# detector328p-au.net
KiCad netlist of a schematic drawn in EAGLE
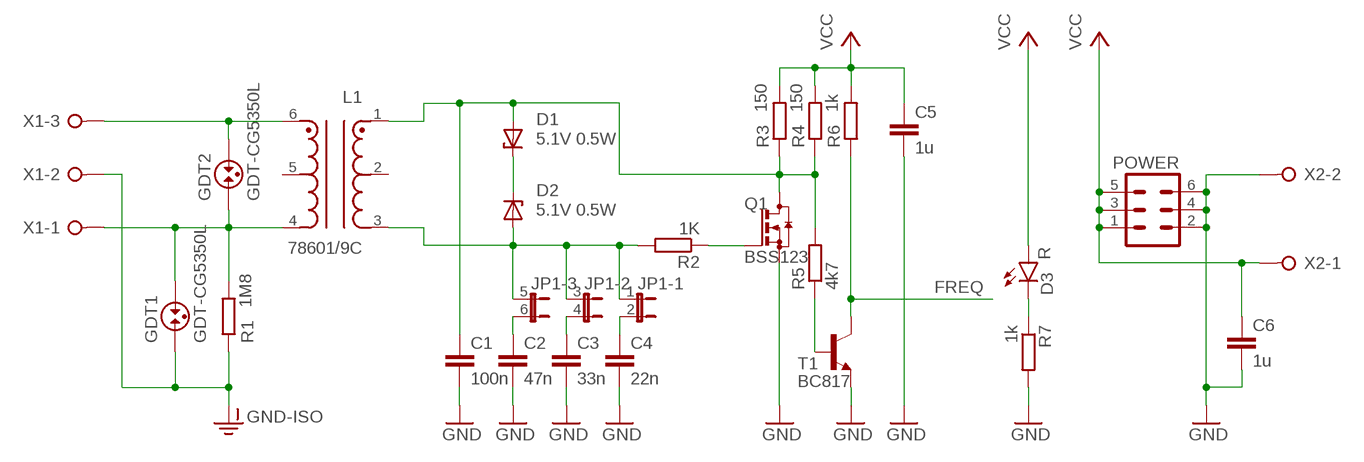
[diagram p0: schematic, sheet 1]
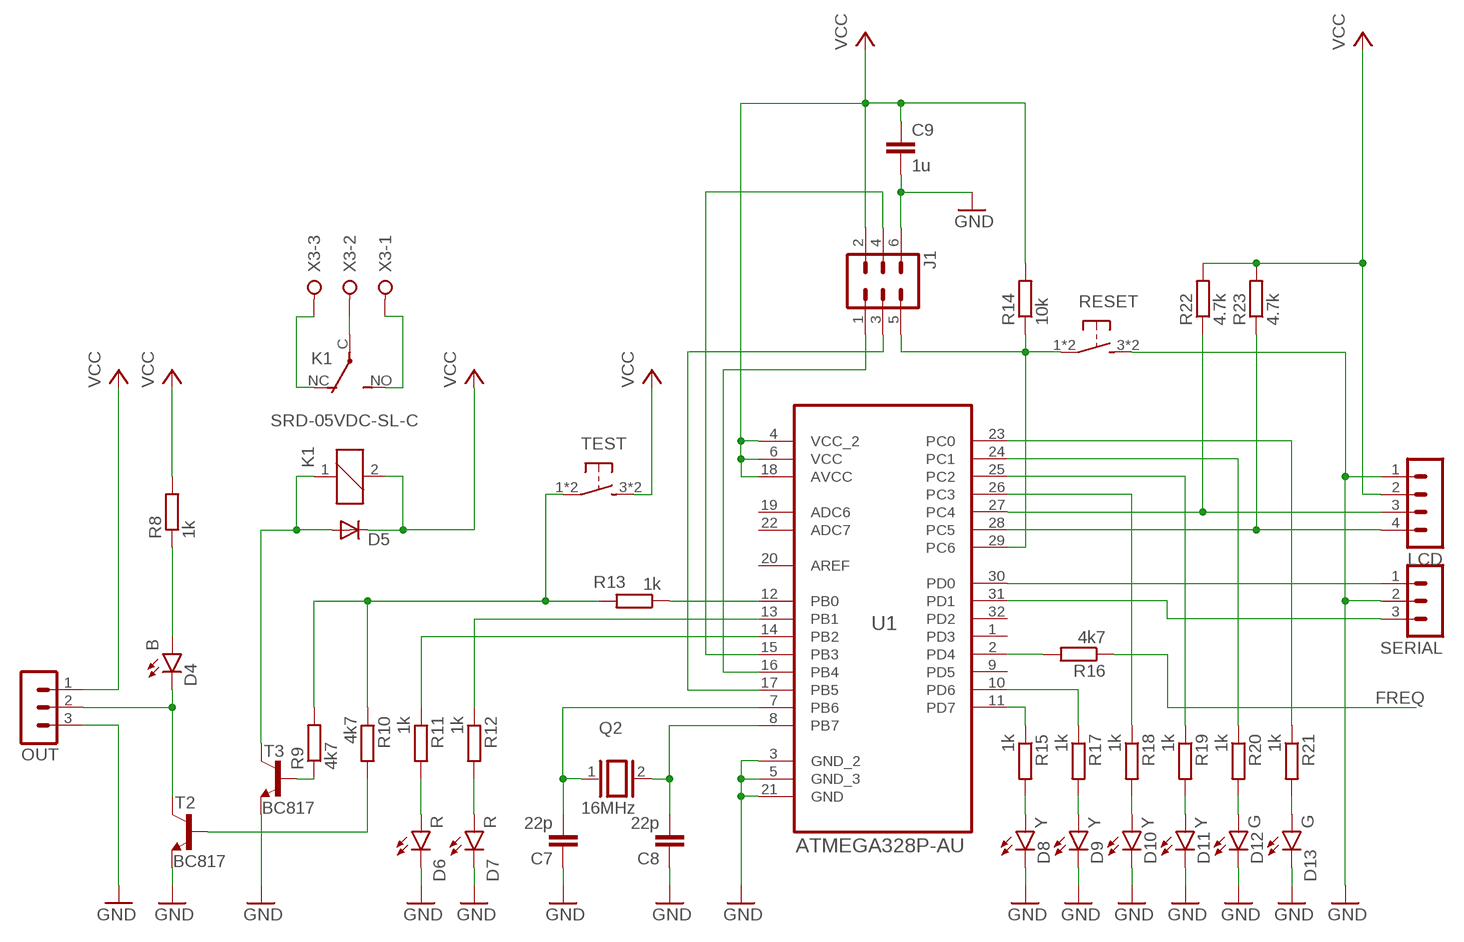
[diagram p1: schematic, sheet 2]

(export (version "E")
  (design (tool "Eeschema 10.0.6"))
  (components
    (comp (ref "C1")
      (value "100n")
      (footprint "eagle-import:C0603")
      (libsource (lib "eagle-import") (part "resistor_C-EUC0603"))
    )
    (comp (ref "C2")
      (value "47n")
      (footprint "eagle-import:C0603")
      (libsource (lib "eagle-import") (part "resistor_C-EUC0603"))
    )
    (comp (ref "C3")
      (value "33n")
      (footprint "eagle-import:C0603")
      (libsource (lib "eagle-import") (part "resistor_C-EUC0603"))
    )
    (comp (ref "C4")
      (value "22n")
      (footprint "eagle-import:C0603")
      (libsource (lib "eagle-import") (part "resistor_C-EUC0603"))
    )
    (comp (ref "C5")
      (value "1u")
      (footprint "eagle-import:C0603")
      (libsource (lib "eagle-import") (part "C-EUC0603"))
    )
    (comp (ref "C6")
      (value "1u")
      (footprint "eagle-import:C0603")
      (libsource (lib "eagle-import") (part "C-EUC0603"))
    )
    (comp (ref "D1")
      (value "5.1V 0.5W")
      (footprint "eagle-import:SOD80C")
      (libsource (lib "eagle-import") (part "ZENER-DIODESOD80C"))
    )
    (comp (ref "D2")
      (value "5.1V 0.5W")
      (footprint "eagle-import:SOD80C")
      (libsource (lib "eagle-import") (part "ZENER-DIODESOD80C"))
    )
    (comp (ref "D3")
      (value "R")
      (footprint "eagle-import:LED-0603")
      (libsource (lib "eagle-import") (part "LED0603"))
    )
    (comp (ref "GDT1")
      (value "GDT-CG5350L")
      (footprint "eagle-import:CG5350L")
      (libsource (lib "eagle-import") (part "GDT-CG5350L"))
    )
    (comp (ref "GDT2")
      (value "GDT-CG5350L")
      (footprint "eagle-import:CG5350L")
      (libsource (lib "eagle-import") (part "GDT-CG5350L"))
    )
    (comp (ref "JP1")
      (value "JP3QE")
      (footprint "eagle-import:JP3Q")
      (libsource (lib "eagle-import") (part "JP3QE"))
    )
    (comp (ref "L1")
      (value "78601/9C")
      (footprint "eagle-import:78601_9C")
      (libsource (lib "eagle-import") (part "78601/9C"))
    )
    (comp (ref "POWER")
      (value "MA03-2")
      (footprint "eagle-import:MA03-2")
      (libsource (lib "eagle-import") (part "MA03-2"))
    )
    (comp (ref "Q1")
      (value "BSS123")
      (footprint "eagle-import:SOT23")
      (libsource (lib "eagle-import") (part "BSS123"))
    )
    (comp (ref "R1")
      (value "1M8")
      (footprint "eagle-import:R0603")
      (libsource (lib "eagle-import") (part "resistor_R-EU_R0603"))
    )
    (comp (ref "R2")
      (value "1K")
      (footprint "eagle-import:R0603")
      (libsource (lib "eagle-import") (part "resistor_R-EU_R0603"))
    )
    (comp (ref "R3")
      (value "150")
      (footprint "eagle-import:R0603")
      (libsource (lib "eagle-import") (part "resistor_R-EU_R0603"))
    )
    (comp (ref "R4")
      (value "150")
      (footprint "eagle-import:R0603")
      (libsource (lib "eagle-import") (part "resistor_R-EU_R0603"))
    )
    (comp (ref "R5")
      (value "4k7")
      (footprint "eagle-import:R0603")
      (libsource (lib "eagle-import") (part "resistor_R-EU_R0603"))
    )
    (comp (ref "R6")
      (value "1k")
      (footprint "eagle-import:R0603")
      (libsource (lib "eagle-import") (part "resistor_R-EU_R0603"))
    )
    (comp (ref "R7")
      (value "1k")
      (footprint "eagle-import:R0603")
      (libsource (lib "eagle-import") (part "resistor_R-EU_R0603"))
    )
    (comp (ref "T1")
      (value "BC817")
      (footprint "eagle-import:SOT23-BEC")
      (libsource (lib "eagle-import") (part "BC817SMD-40"))
    )
    (comp (ref "X1")
      (value "W237-3E")
      (footprint "eagle-import:W237-3E")
      (libsource (lib "eagle-import") (part "W237-3E"))
    )
    (comp (ref "X2")
      (value "W237-02P")
      (footprint "eagle-import:W237-132")
      (libsource (lib "eagle-import") (part "W237-02P"))
    )
    (comp (ref "C7")
      (value "22p")
      (footprint "eagle-import:C0603")
      (libsource (lib "eagle-import") (part "resistor_C-EUC0603"))
    )
    (comp (ref "C8")
      (value "22p")
      (footprint "eagle-import:C0603")
      (libsource (lib "eagle-import") (part "resistor_C-EUC0603"))
    )
    (comp (ref "C9")
      (value "1u")
      (footprint "eagle-import:C0603")
      (libsource (lib "eagle-import") (part "C-EUC0603"))
    )
    (comp (ref "D4")
      (value "B")
      (footprint "eagle-import:LED-0603")
      (libsource (lib "eagle-import") (part "LED0603"))
    )
    (comp (ref "D5")
      (value "DIODE-SOD80C")
      (footprint "eagle-import:SOD80C")
      (libsource (lib "eagle-import") (part "DIODE-SOD80C"))
    )
    (comp (ref "D6")
      (value "R")
      (footprint "eagle-import:LED-0603")
      (libsource (lib "eagle-import") (part "LED0603"))
    )
    (comp (ref "D7")
      (value "R")
      (footprint "eagle-import:LED-0603")
      (libsource (lib "eagle-import") (part "LED0603"))
    )
    (comp (ref "D8")
      (value "Y")
      (footprint "eagle-import:LED-0603")
      (libsource (lib "eagle-import") (part "LED0603"))
    )
    (comp (ref "D9")
      (value "Y")
      (footprint "eagle-import:LED-0603")
      (libsource (lib "eagle-import") (part "LED0603"))
    )
    (comp (ref "D10")
      (value "Y")
      (footprint "eagle-import:LED-0603")
      (libsource (lib "eagle-import") (part "LED0603"))
    )
    (comp (ref "D11")
      (value "Y")
      (footprint "eagle-import:LED-0603")
      (libsource (lib "eagle-import") (part "LED0603"))
    )
    (comp (ref "D12")
      (value "G")
      (footprint "eagle-import:LED-0603")
      (libsource (lib "eagle-import") (part "LED0603"))
    )
    (comp (ref "D13")
      (value "G")
      (footprint "eagle-import:LED-0603")
      (libsource (lib "eagle-import") (part "LED0603"))
    )
    (comp (ref "J1")
      (value "MA03-2")
      (footprint "eagle-import:MA03-2")
      (libsource (lib "eagle-import") (part "MA03-2"))
    )
    (comp (ref "K1")
      (value "SRD-05VDC-SL-C")
      (footprint "eagle-import:JS-M")
      (libsource (lib "eagle-import") (part "SRD--SL-C05VDC"))
    )
    (comp (ref "LCD")
      (value "MA04-1")
      (footprint "eagle-import:MA04-1")
      (libsource (lib "eagle-import") (part "MA04-1"))
    )
    (comp (ref "OUT")
      (value "MA03-1")
      (footprint "eagle-import:MA03-1")
      (libsource (lib "eagle-import") (part "MA03-1"))
    )
    (comp (ref "Q2")
      (value "16MHz")
      (footprint "eagle-import:QS")
      (libsource (lib "eagle-import") (part "XTAL/S"))
    )
    (comp (ref "R8")
      (value "1k")
      (footprint "eagle-import:R0603")
      (libsource (lib "eagle-import") (part "resistor_R-EU_R0603"))
    )
    (comp (ref "R9")
      (value "4k7")
      (footprint "eagle-import:R0603")
      (libsource (lib "eagle-import") (part "resistor_R-EU_R0603"))
    )
    (comp (ref "R10")
      (value "4k7")
      (footprint "eagle-import:R0603")
      (libsource (lib "eagle-import") (part "resistor_R-EU_R0603"))
    )
    (comp (ref "R11")
      (value "1k")
      (footprint "eagle-import:R0603")
      (libsource (lib "eagle-import") (part "resistor_R-EU_R0603"))
    )
    (comp (ref "R12")
      (value "1k")
      (footprint "eagle-import:R0603")
      (libsource (lib "eagle-import") (part "resistor_R-EU_R0603"))
    )
    (comp (ref "R13")
      (value "1k")
      (footprint "eagle-import:R0603")
      (libsource (lib "eagle-import") (part "resistor_R-EU_R0603"))
    )
    (comp (ref "R14")
      (value "10k")
      (footprint "eagle-import:R0603")
      (libsource (lib "eagle-import") (part "resistor_R-EU_R0603"))
    )
    (comp (ref "R15")
      (value "1k")
      (footprint "eagle-import:R0603")
      (libsource (lib "eagle-import") (part "resistor_R-EU_R0603"))
    )
    (comp (ref "R16")
      (value "4k7")
      (footprint "eagle-import:R0603")
      (libsource (lib "eagle-import") (part "resistor_R-EU_R0603"))
    )
    (comp (ref "R17")
      (value "1k")
      (footprint "eagle-import:R0603")
      (libsource (lib "eagle-import") (part "resistor_R-EU_R0603"))
    )
    (comp (ref "R18")
      (value "1k")
      (footprint "eagle-import:R0603")
      (libsource (lib "eagle-import") (part "resistor_R-EU_R0603"))
    )
    (comp (ref "R19")
      (value "1k")
      (footprint "eagle-import:R0603")
      (libsource (lib "eagle-import") (part "resistor_R-EU_R0603"))
    )
    (comp (ref "R20")
      (value "1k")
      (footprint "eagle-import:R0603")
      (libsource (lib "eagle-import") (part "resistor_R-EU_R0603"))
    )
    (comp (ref "R21")
      (value "1k")
      (footprint "eagle-import:R0603")
      (libsource (lib "eagle-import") (part "resistor_R-EU_R0603"))
    )
    (comp (ref "R22")
      (value "4.7k")
      (footprint "eagle-import:R0603")
      (libsource (lib "eagle-import") (part "R-EU_R0603"))
    )
    (comp (ref "R23")
      (value "4.7k")
      (footprint "eagle-import:R0603")
      (libsource (lib "eagle-import") (part "R-EU_R0603"))
    )
    (comp (ref "RESET")
      (value "10-XX")
      (footprint "eagle-import:B3F-10XX")
      (fields (field (name "MPN") "B3F-1000"))
      (libsource (lib "eagle-import") (part "10-XX"))
    )
    (comp (ref "SERIAL")
      (value "MA03-1")
      (footprint "eagle-import:MA03-1")
      (libsource (lib "eagle-import") (part "MA03-1"))
    )
    (comp (ref "T2")
      (value "BC817")
      (footprint "eagle-import:SOT23-BEC")
      (libsource (lib "eagle-import") (part "BC817SMD-40"))
    )
    (comp (ref "T3")
      (value "BC817")
      (footprint "eagle-import:SOT23-BEC")
      (libsource (lib "eagle-import") (part "BC817SMD-40"))
    )
    (comp (ref "TEST")
      (value "10-XX")
      (footprint "eagle-import:B3F-10XX")
      (fields (field (name "MPN") "B3F-1000"))
      (libsource (lib "eagle-import") (part "10-XX"))
    )
    (comp (ref "U1")
      (value "ATMEGA328P-AU")
      (footprint "eagle-import:QFP80P900X900X120-32N")
      (libsource (lib "eagle-import") (part "ATMEGA328P-AU"))
    )
    (comp (ref "X3")
      (value "W237-3E")
      (footprint "eagle-import:W237-3E")
      (libsource (lib "eagle-import") (part "W237-3E"))
    )
  )
  (nets
    (net (code "1") (name "FREQ") (class "Default")
      (node (ref "R16") (pin "1") (pinfunction "1_1") (pintype "passive"))
      (node (ref "R6") (pin "1") (pinfunction "1_1") (pintype "passive"))
      (node (ref "T1") (pin "C") (pinfunction "C_C") (pintype "passive"))
    )
    (net (code "2") (name "GND") (class "Default")
      (node (ref "C1") (pin "2") (pinfunction "2_2") (pintype "passive"))
      (node (ref "C2") (pin "2") (pinfunction "2_2") (pintype "passive"))
      (node (ref "C3") (pin "2") (pinfunction "2_2") (pintype "passive"))
      (node (ref "C4") (pin "2") (pinfunction "2_2") (pintype "passive"))
      (node (ref "C5") (pin "2") (pinfunction "2_2") (pintype "passive"))
      (node (ref "C6") (pin "2") (pinfunction "2_2") (pintype "passive"))
      (node (ref "C7") (pin "1") (pinfunction "1_1") (pintype "passive"))
      (node (ref "C8") (pin "1") (pinfunction "1_1") (pintype "passive"))
      (node (ref "C9") (pin "2") (pinfunction "2_2") (pintype "passive"))
      (node (ref "D10") (pin "C") (pinfunction "C_C") (pintype "passive"))
      (node (ref "D11") (pin "C") (pinfunction "C_C") (pintype "passive"))
      (node (ref "D12") (pin "C") (pinfunction "C_C") (pintype "passive"))
      (node (ref "D13") (pin "C") (pinfunction "C_C") (pintype "passive"))
      (node (ref "D6") (pin "C") (pinfunction "C_C") (pintype "passive"))
      (node (ref "D7") (pin "C") (pinfunction "C_C") (pintype "passive"))
      (node (ref "D8") (pin "C") (pinfunction "C_C") (pintype "passive"))
      (node (ref "D9") (pin "C") (pinfunction "C_C") (pintype "passive"))
      (node (ref "J1") (pin "6") (pinfunction "6_6") (pintype "passive"))
      (node (ref "LCD") (pin "1") (pinfunction "1_1") (pintype "passive"))
      (node (ref "OUT") (pin "3") (pinfunction "3_3") (pintype "passive"))
      (node (ref "POWER") (pin "2") (pinfunction "2_2") (pintype "passive"))
      (node (ref "POWER") (pin "4") (pinfunction "4_4") (pintype "passive"))
      (node (ref "POWER") (pin "6") (pinfunction "6_6") (pintype "passive"))
      (node (ref "Q1") (pin "2") (pinfunction "S_2") (pintype "passive"))
      (node (ref "R7") (pin "2") (pinfunction "2_2") (pintype "passive"))
      (node (ref "RESET") (pin "3") (pinfunction "S_3") (pintype "passive"))
      (node (ref "RESET") (pin "4") (pinfunction "S_4") (pintype "passive"))
      (node (ref "SERIAL") (pin "2") (pinfunction "2_2") (pintype "passive"))
      (node (ref "T1") (pin "E") (pinfunction "E_E") (pintype "passive"))
      (node (ref "T2") (pin "E") (pinfunction "E_E") (pintype "passive"))
      (node (ref "T3") (pin "E") (pinfunction "E_E") (pintype "passive"))
      (node (ref "U1") (pin "21") (pinfunction "GND_21") (pintype "passive"))
      (node (ref "U1") (pin "3") (pinfunction "GND_2_3") (pintype "passive"))
      (node (ref "U1") (pin "5") (pinfunction "GND_3_5") (pintype "passive"))
      (node (ref "X2") (pin "2") (pinfunction "KL_2") (pintype "passive"))
    )
    (net (code "3") (name "GND-ISO") (class "Default")
      (node (ref "GDT1") (pin "1") (pinfunction "1_1") (pintype "passive"))
      (node (ref "R1") (pin "1") (pinfunction "1_1") (pintype "passive"))
      (node (ref "X1") (pin "2") (pinfunction "KL_2") (pintype "passive"))
    )
    (net (code "4") (name "Net-(C4-Pad1)") (class "Default")
      (node (ref "C4") (pin "1") (pinfunction "1_1") (pintype "passive"))
      (node (ref "JP1") (pin "2") (pinfunction "2_2") (pintype "passive"))
    )
    (net (code "5") (name "Net-(D1-PadC)") (class "Default")
      (node (ref "D1") (pin "C") (pinfunction "C_C") (pintype "passive"))
      (node (ref "D2") (pin "C") (pinfunction "C_C") (pintype "passive"))
    )
    (net (code "6") (name "Net-(D3-PadC)") (class "Default")
      (node (ref "D3") (pin "C") (pinfunction "C_C") (pintype "passive"))
      (node (ref "R7") (pin "1") (pinfunction "1_1") (pintype "passive"))
    )
    (net (code "7") (name "Net-(D4-PadA)") (class "Default")
      (node (ref "D4") (pin "A") (pinfunction "A_A") (pintype "passive"))
      (node (ref "R8") (pin "1") (pinfunction "1_1") (pintype "passive"))
    )
    (net (code "8") (name "Net-(D4-PadC)") (class "Default")
      (node (ref "D4") (pin "C") (pinfunction "C_C") (pintype "passive"))
      (node (ref "OUT") (pin "2") (pinfunction "2_2") (pintype "passive"))
      (node (ref "T2") (pin "C") (pinfunction "C_C") (pintype "passive"))
    )
    (net (code "9") (name "Net-(D5-PadA)") (class "Default")
      (node (ref "D5") (pin "A") (pinfunction "A_A") (pintype "passive"))
      (node (ref "K1") (pin "1") (pinfunction "1_1") (pintype "passive"))
      (node (ref "T3") (pin "C") (pinfunction "C_C") (pintype "passive"))
    )
    (net (code "10") (name "Net-(D6-PadA)") (class "Default")
      (node (ref "D6") (pin "A") (pinfunction "A_A") (pintype "passive"))
      (node (ref "R11") (pin "2") (pinfunction "2_2") (pintype "passive"))
    )
    (net (code "11") (name "Net-(D7-PadA)") (class "Default")
      (node (ref "D7") (pin "A") (pinfunction "A_A") (pintype "passive"))
      (node (ref "R12") (pin "2") (pinfunction "2_2") (pintype "passive"))
    )
    (net (code "12") (name "Net-(D8-PadA)") (class "Default")
      (node (ref "D8") (pin "A") (pinfunction "A_A") (pintype "passive"))
      (node (ref "R15") (pin "2") (pinfunction "2_2") (pintype "passive"))
    )
    (net (code "13") (name "Net-(D9-PadA)") (class "Default")
      (node (ref "D9") (pin "A") (pinfunction "A_A") (pintype "passive"))
      (node (ref "R17") (pin "2") (pinfunction "2_2") (pintype "passive"))
    )
    (net (code "14") (name "Net-(D10-PadA)") (class "Default")
      (node (ref "D10") (pin "A") (pinfunction "A_A") (pintype "passive"))
      (node (ref "R18") (pin "2") (pinfunction "2_2") (pintype "passive"))
    )
    (net (code "15") (name "Net-(D11-PadA)") (class "Default")
      (node (ref "D11") (pin "A") (pinfunction "A_A") (pintype "passive"))
      (node (ref "R19") (pin "2") (pinfunction "2_2") (pintype "passive"))
    )
    (net (code "16") (name "Net-(D12-PadA)") (class "Default")
      (node (ref "D12") (pin "A") (pinfunction "A_A") (pintype "passive"))
      (node (ref "R20") (pin "2") (pinfunction "2_2") (pintype "passive"))
    )
    (net (code "17") (name "Net-(D13-PadA)") (class "Default")
      (node (ref "D13") (pin "A") (pinfunction "A_A") (pintype "passive"))
      (node (ref "R21") (pin "2") (pinfunction "2_2") (pintype "passive"))
    )
    (net (code "18") (name "Net-(JP1B-1)") (class "Default")
      (node (ref "D2") (pin "A") (pinfunction "A_A") (pintype "passive"))
      (node (ref "JP1") (pin "1") (pinfunction "1_1") (pintype "passive"))
      (node (ref "JP1") (pin "3") (pinfunction "1_3") (pintype "passive"))
      (node (ref "JP1") (pin "5") (pinfunction "1_5") (pintype "passive"))
      (node (ref "L1") (pin "3") (pinfunction "3_3") (pintype "passive"))
      (node (ref "R2") (pin "2") (pinfunction "2_2") (pintype "passive"))
    )
    (net (code "19") (name "Net-(JP1B-2)") (class "Default")
      (node (ref "C3") (pin "1") (pinfunction "1_1") (pintype "passive"))
      (node (ref "JP1") (pin "4") (pinfunction "2_4") (pintype "passive"))
    )
    (net (code "20") (name "Net-(JP1C-2)") (class "Default")
      (node (ref "C2") (pin "1") (pinfunction "1_1") (pintype "passive"))
      (node (ref "JP1") (pin "6") (pinfunction "2_6") (pintype "passive"))
    )
    (net (code "21") (name "Net-(K1B-O)") (class "Default")
      (node (ref "K1") (pin "NC") (pinfunction "O_NC") (pintype "passive"))
      (node (ref "X3") (pin "3") (pinfunction "KL_3") (pintype "passive"))
    )
    (net (code "22") (name "Net-(K1B-P)") (class "Default")
      (node (ref "K1") (pin "C") (pinfunction "P_C") (pintype "passive"))
      (node (ref "X3") (pin "2") (pinfunction "KL_2") (pintype "passive"))
    )
    (net (code "23") (name "Net-(K1B-S)") (class "Default")
      (node (ref "K1") (pin "NO") (pinfunction "S_NO") (pintype "passive"))
      (node (ref "X3") (pin "1") (pinfunction "KL_1") (pintype "passive"))
    )
    (net (code "24") (name "Net-(Q1-D)") (class "Default")
      (node (ref "C1") (pin "1") (pinfunction "1_1") (pintype "passive"))
      (node (ref "D1") (pin "A") (pinfunction "A_A") (pintype "passive"))
      (node (ref "L1") (pin "1") (pinfunction "1_1") (pintype "passive"))
      (node (ref "Q1") (pin "3") (pinfunction "D_3") (pintype "passive"))
      (node (ref "R3") (pin "1") (pinfunction "1_1") (pintype "passive"))
      (node (ref "R4") (pin "1") (pinfunction "1_1") (pintype "passive"))
      (node (ref "R5") (pin "2") (pinfunction "2_2") (pintype "passive"))
    )
    (net (code "25") (name "Net-(Q1-G)") (class "Default")
      (node (ref "Q1") (pin "1") (pinfunction "G_1") (pintype "passive"))
      (node (ref "R2") (pin "1") (pinfunction "1_1") (pintype "passive"))
    )
    (net (code "26") (name "Net-(R5-Pad1)") (class "Default")
      (node (ref "R5") (pin "1") (pinfunction "1_1") (pintype "passive"))
      (node (ref "T1") (pin "B") (pinfunction "B_B") (pintype "passive"))
    )
    (net (code "27") (name "Net-(R9-Pad1)") (class "Default")
      (node (ref "R9") (pin "1") (pinfunction "1_1") (pintype "passive"))
      (node (ref "T3") (pin "B") (pinfunction "B_B") (pintype "passive"))
    )
    (net (code "28") (name "Net-(R10-Pad1)") (class "Default")
      (node (ref "R10") (pin "1") (pinfunction "1_1") (pintype "passive"))
      (node (ref "R13") (pin "2") (pinfunction "2_2") (pintype "passive"))
      (node (ref "R9") (pin "2") (pinfunction "2_2") (pintype "passive"))
      (node (ref "TEST") (pin "1") (pinfunction "P_1") (pintype "passive"))
      (node (ref "TEST") (pin "2") (pinfunction "P_2") (pintype "passive"))
    )
    (net (code "29") (name "Net-(R10-Pad2)") (class "Default")
      (node (ref "R10") (pin "2") (pinfunction "2_2") (pintype "passive"))
      (node (ref "T2") (pin "B") (pinfunction "B_B") (pintype "passive"))
    )
    (net (code "30") (name "Net-(U1-PB0)") (class "Default")
      (node (ref "R13") (pin "1") (pinfunction "1_1") (pintype "passive"))
      (node (ref "U1") (pin "12") (pinfunction "PB0_12") (pintype "bidirectional"))
    )
    (net (code "31") (name "Net-(U1-PB1)") (class "Default")
      (node (ref "R12") (pin "1") (pinfunction "1_1") (pintype "passive"))
      (node (ref "U1") (pin "13") (pinfunction "PB1_13") (pintype "bidirectional"))
    )
    (net (code "32") (name "Net-(U1-PB2)") (class "Default")
      (node (ref "R11") (pin "1") (pinfunction "1_1") (pintype "passive"))
      (node (ref "U1") (pin "14") (pinfunction "PB2_14") (pintype "bidirectional"))
    )
    (net (code "33") (name "Net-(U1-PB3)") (class "Default")
      (node (ref "J1") (pin "4") (pinfunction "4_4") (pintype "passive"))
      (node (ref "U1") (pin "15") (pinfunction "PB3_15") (pintype "bidirectional"))
    )
    (net (code "34") (name "Net-(U1-PB4)") (class "Default")
      (node (ref "J1") (pin "1") (pinfunction "1_1") (pintype "passive"))
      (node (ref "U1") (pin "16") (pinfunction "PB4_16") (pintype "bidirectional"))
    )
    (net (code "35") (name "Net-(U1-PB5)") (class "Default")
      (node (ref "J1") (pin "3") (pinfunction "3_3") (pintype "passive"))
      (node (ref "U1") (pin "17") (pinfunction "PB5_17") (pintype "bidirectional"))
    )
    (net (code "36") (name "Net-(U1-PB6)") (class "Default")
      (node (ref "C7") (pin "2") (pinfunction "2_2") (pintype "passive"))
      (node (ref "Q2") (pin "1") (pinfunction "1_1") (pintype "passive"))
      (node (ref "U1") (pin "7") (pinfunction "PB6_7") (pintype "bidirectional"))
    )
    (net (code "37") (name "Net-(U1-PB7)") (class "Default")
      (node (ref "C8") (pin "2") (pinfunction "2_2") (pintype "passive"))
      (node (ref "Q2") (pin "2") (pinfunction "2_2") (pintype "passive"))
      (node (ref "U1") (pin "8") (pinfunction "PB7_8") (pintype "bidirectional"))
    )
    (net (code "38") (name "Net-(U1-PC0)") (class "Default")
      (node (ref "R21") (pin "1") (pinfunction "1_1") (pintype "passive"))
      (node (ref "U1") (pin "23") (pinfunction "PC0_23") (pintype "bidirectional"))
    )
    (net (code "39") (name "Net-(U1-PC1)") (class "Default")
      (node (ref "R20") (pin "1") (pinfunction "1_1") (pintype "passive"))
      (node (ref "U1") (pin "24") (pinfunction "PC1_24") (pintype "bidirectional"))
    )
    (net (code "40") (name "Net-(U1-PC2)") (class "Default")
      (node (ref "R19") (pin "1") (pinfunction "1_1") (pintype "passive"))
      (node (ref "U1") (pin "25") (pinfunction "PC2_25") (pintype "bidirectional"))
    )
    (net (code "41") (name "Net-(U1-PC3)") (class "Default")
      (node (ref "R18") (pin "1") (pinfunction "1_1") (pintype "passive"))
      (node (ref "U1") (pin "26") (pinfunction "PC3_26") (pintype "bidirectional"))
    )
    (net (code "42") (name "Net-(U1-PC4)") (class "Default")
      (node (ref "LCD") (pin "3") (pinfunction "3_3") (pintype "passive"))
      (node (ref "R22") (pin "1") (pinfunction "1_1") (pintype "passive"))
      (node (ref "U1") (pin "27") (pinfunction "PC4_27") (pintype "bidirectional"))
    )
    (net (code "43") (name "Net-(U1-PC5)") (class "Default")
      (node (ref "LCD") (pin "4") (pinfunction "4_4") (pintype "passive"))
      (node (ref "R23") (pin "1") (pinfunction "1_1") (pintype "passive"))
      (node (ref "U1") (pin "28") (pinfunction "PC5_28") (pintype "bidirectional"))
    )
    (net (code "44") (name "Net-(U1-PC6)") (class "Default")
      (node (ref "J1") (pin "5") (pinfunction "5_5") (pintype "passive"))
      (node (ref "R14") (pin "1") (pinfunction "1_1") (pintype "passive"))
      (node (ref "RESET") (pin "1") (pinfunction "P_1") (pintype "passive"))
      (node (ref "RESET") (pin "2") (pinfunction "P_2") (pintype "passive"))
      (node (ref "U1") (pin "29") (pinfunction "PC6_29") (pintype "bidirectional"))
    )
    (net (code "45") (name "Net-(U1-PD0)") (class "Default")
      (node (ref "SERIAL") (pin "1") (pinfunction "1_1") (pintype "passive"))
      (node (ref "U1") (pin "30") (pinfunction "PD0_30") (pintype "bidirectional"))
    )
    (net (code "46") (name "Net-(U1-PD1)") (class "Default")
      (node (ref "SERIAL") (pin "3") (pinfunction "3_3") (pintype "passive"))
      (node (ref "U1") (pin "31") (pinfunction "PD1_31") (pintype "bidirectional"))
    )
    (net (code "47") (name "Net-(U1-PD4)") (class "Default")
      (node (ref "R16") (pin "2") (pinfunction "2_2") (pintype "passive"))
      (node (ref "U1") (pin "2") (pinfunction "PD4_2") (pintype "bidirectional"))
    )
    (net (code "48") (name "Net-(U1-PD6)") (class "Default")
      (node (ref "R17") (pin "1") (pinfunction "1_1") (pintype "passive"))
      (node (ref "U1") (pin "10") (pinfunction "PD6_10") (pintype "bidirectional"))
    )
    (net (code "49") (name "Net-(U1-PD7)") (class "Default")
      (node (ref "R15") (pin "1") (pinfunction "1_1") (pintype "passive"))
      (node (ref "U1") (pin "11") (pinfunction "PD7_11") (pintype "bidirectional"))
    )
    (net (code "50") (name "Net-(X1A-KL)") (class "Default")
      (node (ref "GDT1") (pin "2") (pinfunction "2_2") (pintype "passive"))
      (node (ref "GDT2") (pin "1") (pinfunction "1_1") (pintype "passive"))
      (node (ref "L1") (pin "4") (pinfunction "4_4") (pintype "passive"))
      (node (ref "R1") (pin "2") (pinfunction "2_2") (pintype "passive"))
      (node (ref "X1") (pin "1") (pinfunction "KL_1") (pintype "passive"))
    )
    (net (code "51") (name "Net-(X1C-KL)") (class "Default")
      (node (ref "GDT2") (pin "2") (pinfunction "2_2") (pintype "passive"))
      (node (ref "L1") (pin "6") (pinfunction "6_6") (pintype "passive"))
      (node (ref "X1") (pin "3") (pinfunction "KL_3") (pintype "passive"))
    )
    (net (code "52") (name "VCC") (class "Default")
      (node (ref "C5") (pin "1") (pinfunction "1_1") (pintype "passive"))
      (node (ref "C6") (pin "1") (pinfunction "1_1") (pintype "passive"))
      (node (ref "C9") (pin "1") (pinfunction "1_1") (pintype "passive"))
      (node (ref "D3") (pin "A") (pinfunction "A_A") (pintype "passive"))
      (node (ref "D5") (pin "C") (pinfunction "C_C") (pintype "passive"))
      (node (ref "J1") (pin "2") (pinfunction "2_2") (pintype "passive"))
      (node (ref "K1") (pin "2") (pinfunction "2_2") (pintype "passive"))
      (node (ref "LCD") (pin "2") (pinfunction "2_2") (pintype "passive"))
      (node (ref "OUT") (pin "1") (pinfunction "1_1") (pintype "passive"))
      (node (ref "POWER") (pin "1") (pinfunction "1_1") (pintype "passive"))
      (node (ref "POWER") (pin "3") (pinfunction "3_3") (pintype "passive"))
      (node (ref "POWER") (pin "5") (pinfunction "5_5") (pintype "passive"))
      (node (ref "R14") (pin "2") (pinfunction "2_2") (pintype "passive"))
      (node (ref "R22") (pin "2") (pinfunction "2_2") (pintype "passive"))
      (node (ref "R23") (pin "2") (pinfunction "2_2") (pintype "passive"))
      (node (ref "R3") (pin "2") (pinfunction "2_2") (pintype "passive"))
      (node (ref "R4") (pin "2") (pinfunction "2_2") (pintype "passive"))
      (node (ref "R6") (pin "2") (pinfunction "2_2") (pintype "passive"))
      (node (ref "R8") (pin "2") (pinfunction "2_2") (pintype "passive"))
      (node (ref "TEST") (pin "3") (pinfunction "S_3") (pintype "passive"))
      (node (ref "TEST") (pin "4") (pinfunction "S_4") (pintype "passive"))
      (node (ref "U1") (pin "18") (pinfunction "AVCC_18") (pintype "power_in"))
      (node (ref "U1") (pin "4") (pinfunction "VCC_2_4") (pintype "power_in"))
      (node (ref "U1") (pin "6") (pinfunction "VCC_6") (pintype "power_in"))
      (node (ref "X2") (pin "1") (pinfunction "KL_1") (pintype "passive"))
    )
    (net (code "53") (name "unconnected-(L1-Pad2)") (class "Default")
      (node (ref "L1") (pin "2") (pinfunction "2_2") (pintype "passive"))
    )
    (net (code "54") (name "unconnected-(L1-Pad5)") (class "Default")
      (node (ref "L1") (pin "5") (pinfunction "5_5") (pintype "passive"))
    )
    (net (code "55") (name "unconnected-(U1-ADC6-Pad19)") (class "Default")
      (node (ref "U1") (pin "19") (pinfunction "ADC6_19") (pintype "input"))
    )
    (net (code "56") (name "unconnected-(U1-ADC7-Pad22)") (class "Default")
      (node (ref "U1") (pin "22") (pinfunction "ADC7_22") (pintype "input"))
    )
    (net (code "57") (name "unconnected-(U1-AREF-Pad20)") (class "Default")
      (node (ref "U1") (pin "20") (pinfunction "AREF_20") (pintype "input"))
    )
    (net (code "58") (name "unconnected-(U1-PD2-Pad32)") (class "Default")
      (node (ref "U1") (pin "32") (pinfunction "PD2_32") (pintype "bidirectional"))
    )
    (net (code "59") (name "unconnected-(U1-PD3-Pad1)") (class "Default")
      (node (ref "U1") (pin "1") (pinfunction "PD3_1") (pintype "bidirectional"))
    )
    (net (code "60") (name "unconnected-(U1-PD5-Pad9)") (class "Default")
      (node (ref "U1") (pin "9") (pinfunction "PD5_9") (pintype "bidirectional"))
    )
  )
)
